# Z80_Interface.net
KiCad netlist of a schematic drawn in Altium Designer
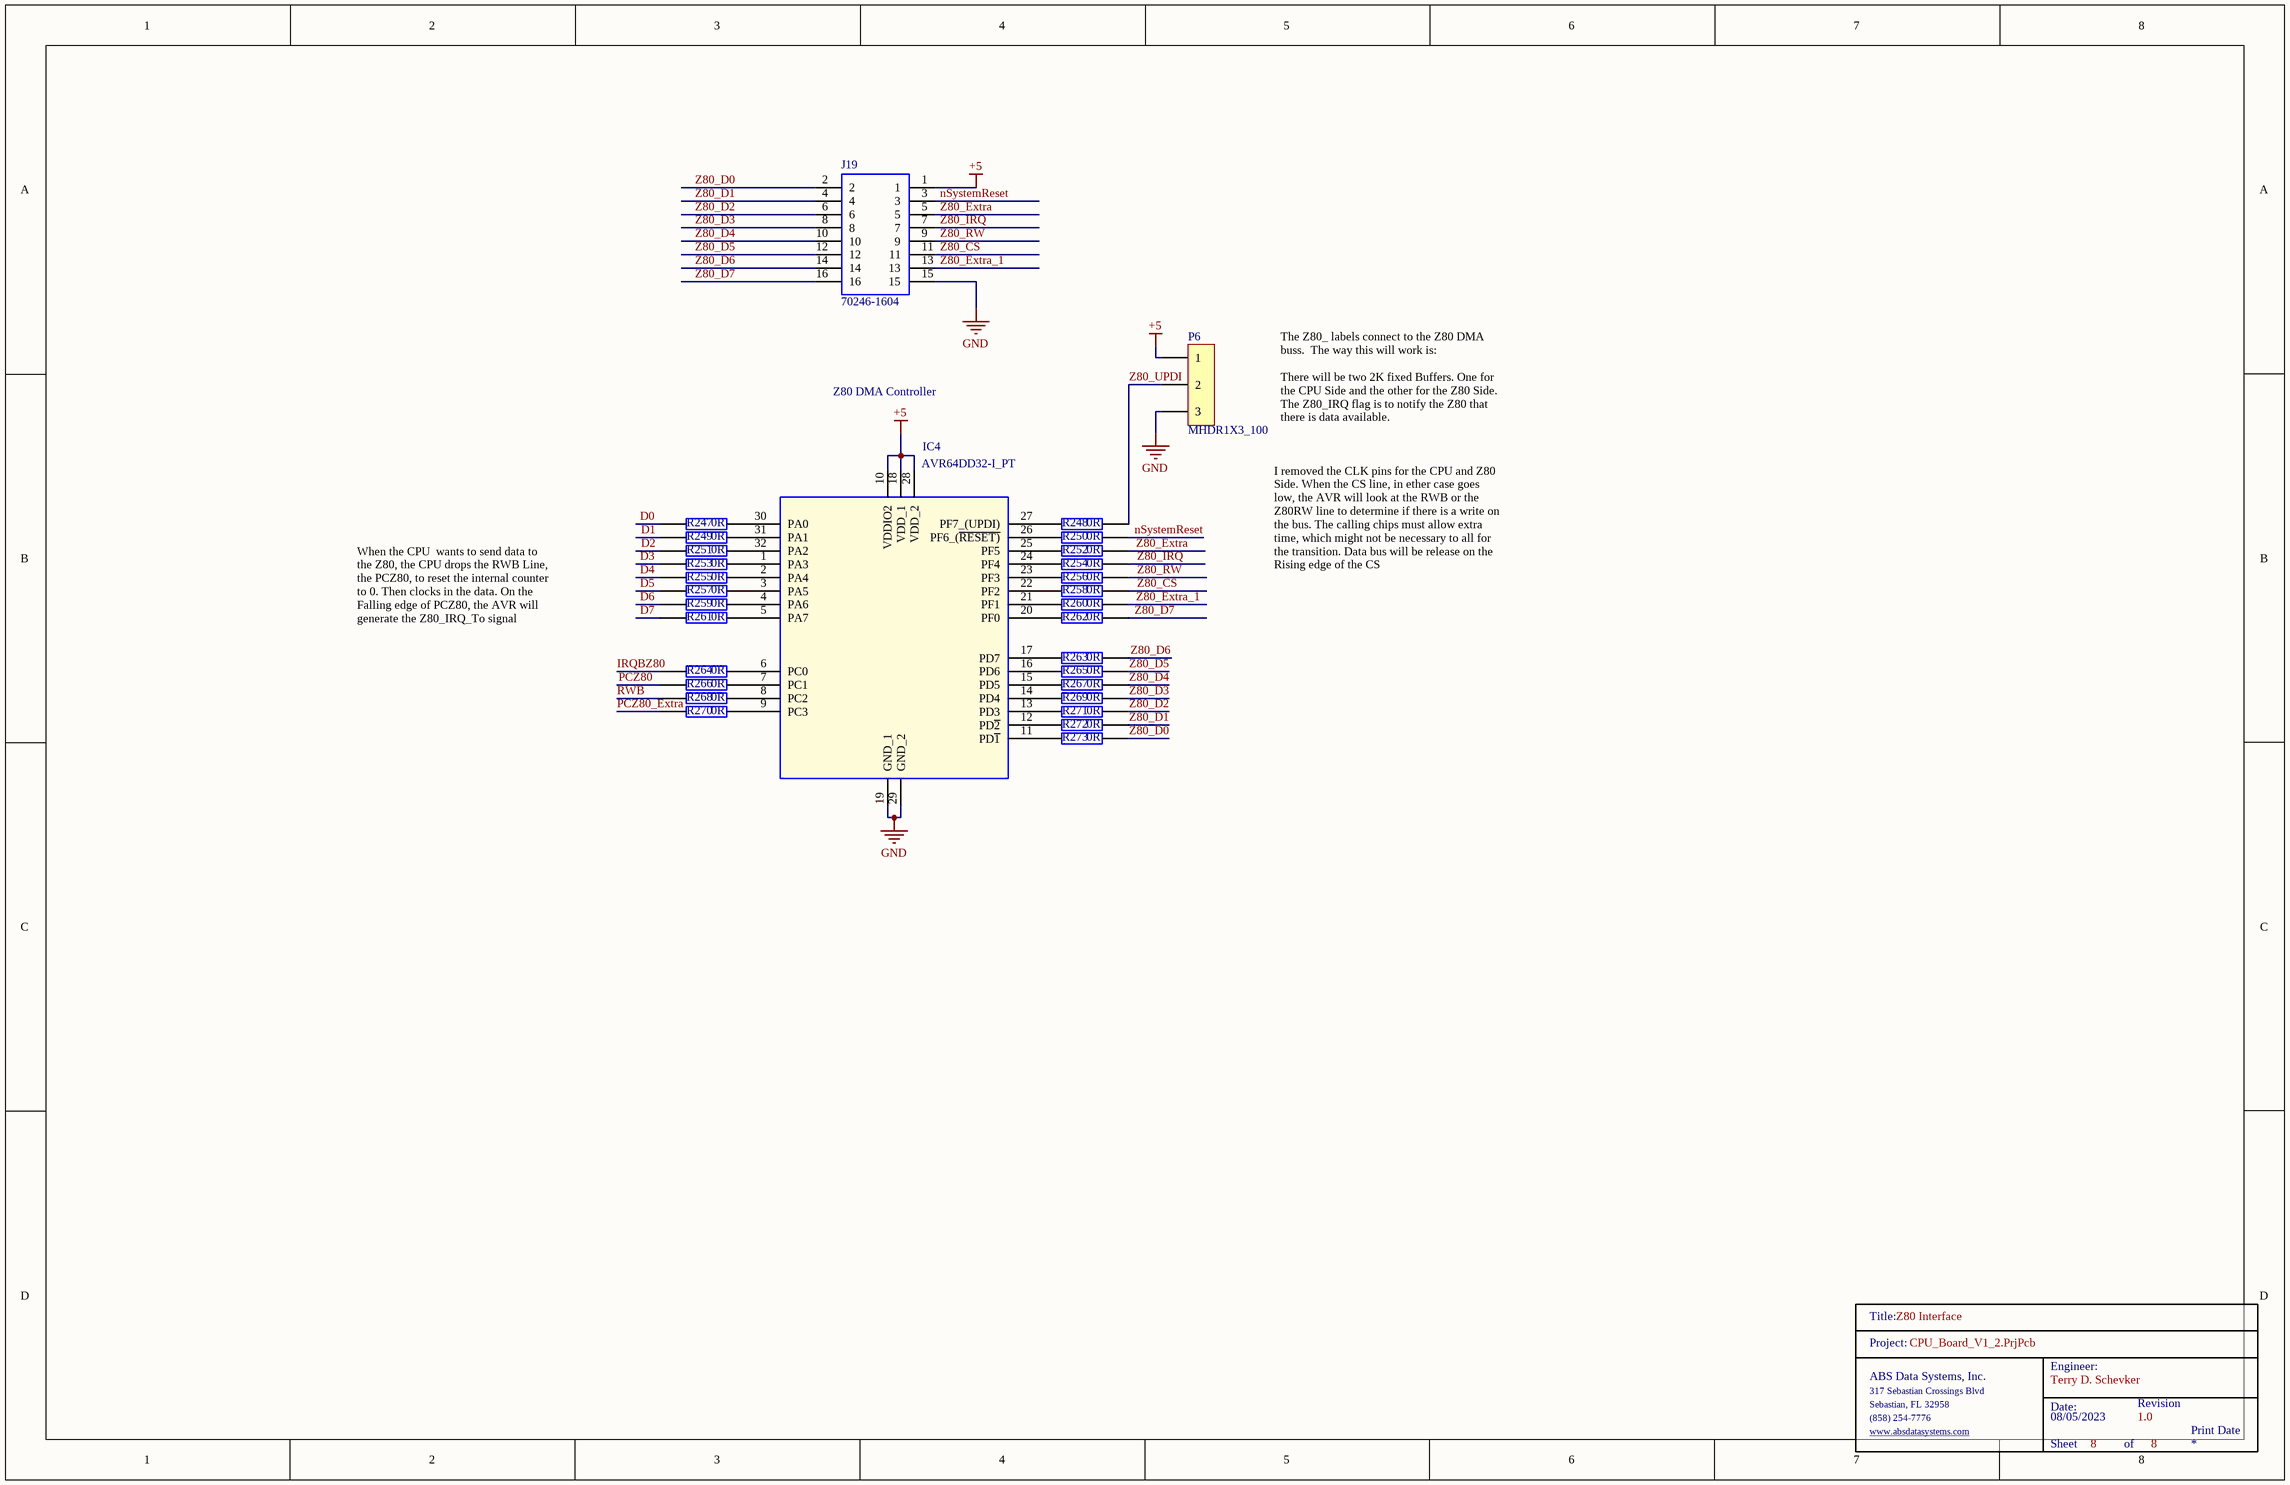
[diagram p0: Z80_Interface.SchDoc]

(export (version "E")
  (design (tool "Eeschema 10.0.6"))
  (components
    (comp (ref "IC4")
      (value "AVR64DD32-I_PT")
      (footprint "CPU_Memory:QFP80P900X900X120-32N")
      (description "Integrated Circuit")
      (fields (field (name "MANUFACTURER_PART_NUMBER") "AVR64DD32-I/PT ¦ MULTI-VOLTAGE I/O"))
      (libsource (lib "CPU_Memory") (part "AVR64DD32-I_PT"))
    )
    (comp (ref "J19")
      (value "70246-1604")
      (footprint "SHDR16W99P254_2X8_2794X889X927P")
      (description "Molex C-GRID 70246, 2.54mm Pitch, 16 Way, 2 Row, Straight PCB Header, Through Hole")
      (fields (field (name "MOUSER PART NUMBER") "538-70246-1604"))
      (libsource (lib "Connectors") (part "70246-1604"))
    )
    (comp (ref "P6")
      (value "MHDR1X3_100")
      (footprint "MHDR1X3_100")
      (description "Header, 3-Pin")
      (fields (field (name "PUBLISHER") "Altium Limited"))
      (libsource (lib "Connectors") (part "MHDR1X3_100"))
    )
    (comp (ref "R247")
      (value "0R")
      (footprint "0603")
      (description "YAGEO 0603 0 ohm")
      (fields
        (field (name "MOUSER PART NUMBER") "603-RC0603JR-070RL")
        (field (name "MANUFACTURER_PART_NUMBER") "RC0603JR-070RL")
      )
      (libsource (lib "Resistors") (part "RC0603JR-070RL"))
    )
    (comp (ref "R248")
      (value "0R")
      (footprint "0603")
      (description "YAGEO 0603 0 ohm")
      (fields
        (field (name "MOUSER PART NUMBER") "603-RC0603JR-070RL")
        (field (name "MANUFACTURER_PART_NUMBER") "RC0603JR-070RL")
      )
      (libsource (lib "Resistors") (part "RC0603JR-070RL"))
    )
    (comp (ref "R249")
      (value "0R")
      (footprint "0603")
      (description "YAGEO 0603 0 ohm")
      (fields
        (field (name "MOUSER PART NUMBER") "603-RC0603JR-070RL")
        (field (name "MANUFACTURER_PART_NUMBER") "RC0603JR-070RL")
      )
      (libsource (lib "Resistors") (part "RC0603JR-070RL"))
    )
    (comp (ref "R250")
      (value "0R")
      (footprint "0603")
      (description "YAGEO 0603 0 ohm")
      (fields
        (field (name "MOUSER PART NUMBER") "603-RC0603JR-070RL")
        (field (name "MANUFACTURER_PART_NUMBER") "RC0603JR-070RL")
      )
      (libsource (lib "Resistors") (part "RC0603JR-070RL"))
    )
    (comp (ref "R251")
      (value "0R")
      (footprint "0603")
      (description "YAGEO 0603 0 ohm")
      (fields
        (field (name "MOUSER PART NUMBER") "603-RC0603JR-070RL")
        (field (name "MANUFACTURER_PART_NUMBER") "RC0603JR-070RL")
      )
      (libsource (lib "Resistors") (part "RC0603JR-070RL"))
    )
    (comp (ref "R252")
      (value "0R")
      (footprint "0603")
      (description "YAGEO 0603 0 ohm")
      (fields
        (field (name "MOUSER PART NUMBER") "603-RC0603JR-070RL")
        (field (name "MANUFACTURER_PART_NUMBER") "RC0603JR-070RL")
      )
      (libsource (lib "Resistors") (part "RC0603JR-070RL"))
    )
    (comp (ref "R253")
      (value "0R")
      (footprint "0603")
      (description "YAGEO 0603 0 ohm")
      (fields
        (field (name "MOUSER PART NUMBER") "603-RC0603JR-070RL")
        (field (name "MANUFACTURER_PART_NUMBER") "RC0603JR-070RL")
      )
      (libsource (lib "Resistors") (part "RC0603JR-070RL"))
    )
    (comp (ref "R254")
      (value "0R")
      (footprint "0603")
      (description "YAGEO 0603 0 ohm")
      (fields
        (field (name "MOUSER PART NUMBER") "603-RC0603JR-070RL")
        (field (name "MANUFACTURER_PART_NUMBER") "RC0603JR-070RL")
      )
      (libsource (lib "Resistors") (part "RC0603JR-070RL"))
    )
    (comp (ref "R255")
      (value "0R")
      (footprint "0603")
      (description "YAGEO 0603 0 ohm")
      (fields
        (field (name "MOUSER PART NUMBER") "603-RC0603JR-070RL")
        (field (name "MANUFACTURER_PART_NUMBER") "RC0603JR-070RL")
      )
      (libsource (lib "Resistors") (part "RC0603JR-070RL"))
    )
    (comp (ref "R256")
      (value "0R")
      (footprint "0603")
      (description "YAGEO 0603 0 ohm")
      (fields
        (field (name "MOUSER PART NUMBER") "603-RC0603JR-070RL")
        (field (name "MANUFACTURER_PART_NUMBER") "RC0603JR-070RL")
      )
      (libsource (lib "Resistors") (part "RC0603JR-070RL"))
    )
    (comp (ref "R257")
      (value "0R")
      (footprint "0603")
      (description "YAGEO 0603 0 ohm")
      (fields
        (field (name "MOUSER PART NUMBER") "603-RC0603JR-070RL")
        (field (name "MANUFACTURER_PART_NUMBER") "RC0603JR-070RL")
      )
      (libsource (lib "Resistors") (part "RC0603JR-070RL"))
    )
    (comp (ref "R258")
      (value "0R")
      (footprint "0603")
      (description "YAGEO 0603 0 ohm")
      (fields
        (field (name "MOUSER PART NUMBER") "603-RC0603JR-070RL")
        (field (name "MANUFACTURER_PART_NUMBER") "RC0603JR-070RL")
      )
      (libsource (lib "Resistors") (part "RC0603JR-070RL"))
    )
    (comp (ref "R259")
      (value "0R")
      (footprint "0603")
      (description "YAGEO 0603 0 ohm")
      (fields
        (field (name "MOUSER PART NUMBER") "603-RC0603JR-070RL")
        (field (name "MANUFACTURER_PART_NUMBER") "RC0603JR-070RL")
      )
      (libsource (lib "Resistors") (part "RC0603JR-070RL"))
    )
    (comp (ref "R260")
      (value "0R")
      (footprint "0603")
      (description "YAGEO 0603 0 ohm")
      (fields
        (field (name "MOUSER PART NUMBER") "603-RC0603JR-070RL")
        (field (name "MANUFACTURER_PART_NUMBER") "RC0603JR-070RL")
      )
      (libsource (lib "Resistors") (part "RC0603JR-070RL"))
    )
    (comp (ref "R261")
      (value "0R")
      (footprint "0603")
      (description "YAGEO 0603 0 ohm")
      (fields
        (field (name "MOUSER PART NUMBER") "603-RC0603JR-070RL")
        (field (name "MANUFACTURER_PART_NUMBER") "RC0603JR-070RL")
      )
      (libsource (lib "Resistors") (part "RC0603JR-070RL"))
    )
    (comp (ref "R262")
      (value "0R")
      (footprint "0603")
      (description "YAGEO 0603 0 ohm")
      (fields
        (field (name "MOUSER PART NUMBER") "603-RC0603JR-070RL")
        (field (name "MANUFACTURER_PART_NUMBER") "RC0603JR-070RL")
      )
      (libsource (lib "Resistors") (part "RC0603JR-070RL"))
    )
    (comp (ref "R263")
      (value "0R")
      (footprint "0603")
      (description "YAGEO 0603 0 ohm")
      (fields
        (field (name "MOUSER PART NUMBER") "603-RC0603JR-070RL")
        (field (name "MANUFACTURER_PART_NUMBER") "RC0603JR-070RL")
      )
      (libsource (lib "Resistors") (part "RC0603JR-070RL"))
    )
    (comp (ref "R264")
      (value "0R")
      (footprint "0603")
      (description "YAGEO 0603 0 ohm")
      (fields
        (field (name "MOUSER PART NUMBER") "603-RC0603JR-070RL")
        (field (name "MANUFACTURER_PART_NUMBER") "RC0603JR-070RL")
      )
      (libsource (lib "Resistors") (part "RC0603JR-070RL"))
    )
    (comp (ref "R265")
      (value "0R")
      (footprint "0603")
      (description "YAGEO 0603 0 ohm")
      (fields
        (field (name "MOUSER PART NUMBER") "603-RC0603JR-070RL")
        (field (name "MANUFACTURER_PART_NUMBER") "RC0603JR-070RL")
      )
      (libsource (lib "Resistors") (part "RC0603JR-070RL"))
    )
    (comp (ref "R266")
      (value "0R")
      (footprint "0603")
      (description "YAGEO 0603 0 ohm")
      (fields
        (field (name "MOUSER PART NUMBER") "603-RC0603JR-070RL")
        (field (name "MANUFACTURER_PART_NUMBER") "RC0603JR-070RL")
      )
      (libsource (lib "Resistors") (part "RC0603JR-070RL"))
    )
    (comp (ref "R267")
      (value "0R")
      (footprint "0603")
      (description "YAGEO 0603 0 ohm")
      (fields
        (field (name "MOUSER PART NUMBER") "603-RC0603JR-070RL")
        (field (name "MANUFACTURER_PART_NUMBER") "RC0603JR-070RL")
      )
      (libsource (lib "Resistors") (part "RC0603JR-070RL"))
    )
    (comp (ref "R268")
      (value "0R")
      (footprint "0603")
      (description "YAGEO 0603 0 ohm")
      (fields
        (field (name "MOUSER PART NUMBER") "603-RC0603JR-070RL")
        (field (name "MANUFACTURER_PART_NUMBER") "RC0603JR-070RL")
      )
      (libsource (lib "Resistors") (part "RC0603JR-070RL"))
    )
    (comp (ref "R269")
      (value "0R")
      (footprint "0603")
      (description "YAGEO 0603 0 ohm")
      (fields
        (field (name "MOUSER PART NUMBER") "603-RC0603JR-070RL")
        (field (name "MANUFACTURER_PART_NUMBER") "RC0603JR-070RL")
      )
      (libsource (lib "Resistors") (part "RC0603JR-070RL"))
    )
    (comp (ref "R270")
      (value "0R")
      (footprint "0603")
      (description "YAGEO 0603 0 ohm")
      (fields
        (field (name "MOUSER PART NUMBER") "603-RC0603JR-070RL")
        (field (name "MANUFACTURER_PART_NUMBER") "RC0603JR-070RL")
      )
      (libsource (lib "Resistors") (part "RC0603JR-070RL"))
    )
    (comp (ref "R271")
      (value "0R")
      (footprint "0603")
      (description "YAGEO 0603 0 ohm")
      (fields
        (field (name "MOUSER PART NUMBER") "603-RC0603JR-070RL")
        (field (name "MANUFACTURER_PART_NUMBER") "RC0603JR-070RL")
      )
      (libsource (lib "Resistors") (part "RC0603JR-070RL"))
    )
    (comp (ref "R272")
      (value "0R")
      (footprint "0603")
      (description "YAGEO 0603 0 ohm")
      (fields
        (field (name "MOUSER PART NUMBER") "603-RC0603JR-070RL")
        (field (name "MANUFACTURER_PART_NUMBER") "RC0603JR-070RL")
      )
      (libsource (lib "Resistors") (part "RC0603JR-070RL"))
    )
    (comp (ref "R273")
      (value "0R")
      (footprint "0603")
      (description "YAGEO 0603 0 ohm")
      (fields
        (field (name "MOUSER PART NUMBER") "603-RC0603JR-070RL")
        (field (name "MANUFACTURER_PART_NUMBER") "RC0603JR-070RL")
      )
      (libsource (lib "Resistors") (part "RC0603JR-070RL"))
    )
  )
  (nets
    (net (code "1") (name "+5") (class "Default")
      (node (ref "IC4") (pin "10") (pinfunction "VDDIO2_10") (pintype "passive"))
      (node (ref "IC4") (pin "18") (pinfunction "VDD_1_18") (pintype "passive"))
      (node (ref "IC4") (pin "28") (pinfunction "VDD_2_28") (pintype "passive"))
      (node (ref "J19") (pin "1") (pinfunction "1_1") (pintype "passive"))
      (node (ref "P6") (pin "1") (pinfunction "1_1") (pintype "passive"))
    )
    (net (code "2") (name "/D0") (class "Default")
      (node (ref "R247") (pin "1") (pinfunction "1_1") (pintype "passive"))
    )
    (net (code "3") (name "/D1") (class "Default")
      (node (ref "R249") (pin "1") (pinfunction "1_1") (pintype "passive"))
    )
    (net (code "4") (name "/D2") (class "Default")
      (node (ref "R251") (pin "1") (pinfunction "1_1") (pintype "passive"))
    )
    (net (code "5") (name "/D3") (class "Default")
      (node (ref "R253") (pin "1") (pinfunction "1_1") (pintype "passive"))
    )
    (net (code "6") (name "/D4") (class "Default")
      (node (ref "R255") (pin "1") (pinfunction "1_1") (pintype "passive"))
    )
    (net (code "7") (name "/D5") (class "Default")
      (node (ref "R257") (pin "1") (pinfunction "1_1") (pintype "passive"))
    )
    (net (code "8") (name "/D6") (class "Default")
      (node (ref "R259") (pin "1") (pinfunction "1_1") (pintype "passive"))
    )
    (net (code "9") (name "/D7") (class "Default")
      (node (ref "R261") (pin "1") (pinfunction "1_1") (pintype "passive"))
    )
    (net (code "10") (name "/IRQBZ80") (class "Default")
      (node (ref "R264") (pin "1") (pinfunction "1_1") (pintype "passive"))
    )
    (net (code "11") (name "/PCZ80") (class "Default")
      (node (ref "R266") (pin "1") (pinfunction "1_1") (pintype "passive"))
    )
    (net (code "12") (name "/PCZ80_Extra") (class "Default")
      (node (ref "R270") (pin "1") (pinfunction "1_1") (pintype "passive"))
    )
    (net (code "13") (name "/RWB") (class "Default")
      (node (ref "R268") (pin "1") (pinfunction "1_1") (pintype "passive"))
    )
    (net (code "14") (name "/Z80_CS") (class "Default")
      (node (ref "J19") (pin "11") (pinfunction "11_11") (pintype "passive"))
      (node (ref "R258") (pin "2") (pinfunction "2_2") (pintype "passive"))
    )
    (net (code "15") (name "/Z80_D0") (class "Default")
      (node (ref "J19") (pin "2") (pinfunction "2_2") (pintype "passive"))
      (node (ref "R273") (pin "2") (pinfunction "2_2") (pintype "passive"))
    )
    (net (code "16") (name "/Z80_D1") (class "Default")
      (node (ref "J19") (pin "4") (pinfunction "4_4") (pintype "passive"))
      (node (ref "R272") (pin "2") (pinfunction "2_2") (pintype "passive"))
    )
    (net (code "17") (name "/Z80_D2") (class "Default")
      (node (ref "J19") (pin "6") (pinfunction "6_6") (pintype "passive"))
      (node (ref "R271") (pin "2") (pinfunction "2_2") (pintype "passive"))
    )
    (net (code "18") (name "/Z80_D3") (class "Default")
      (node (ref "J19") (pin "8") (pinfunction "8_8") (pintype "passive"))
      (node (ref "R269") (pin "2") (pinfunction "2_2") (pintype "passive"))
    )
    (net (code "19") (name "/Z80_D4") (class "Default")
      (node (ref "J19") (pin "10") (pinfunction "10_10") (pintype "passive"))
      (node (ref "R267") (pin "2") (pinfunction "2_2") (pintype "passive"))
    )
    (net (code "20") (name "/Z80_D5") (class "Default")
      (node (ref "J19") (pin "12") (pinfunction "12_12") (pintype "passive"))
      (node (ref "R265") (pin "2") (pinfunction "2_2") (pintype "passive"))
    )
    (net (code "21") (name "/Z80_D6") (class "Default")
      (node (ref "J19") (pin "14") (pinfunction "14_14") (pintype "passive"))
      (node (ref "R263") (pin "2") (pinfunction "2_2") (pintype "passive"))
    )
    (net (code "22") (name "/Z80_D7") (class "Default")
      (node (ref "J19") (pin "16") (pinfunction "16_16") (pintype "passive"))
      (node (ref "R262") (pin "2") (pinfunction "2_2") (pintype "passive"))
    )
    (net (code "23") (name "/Z80_Extra") (class "Default")
      (node (ref "J19") (pin "5") (pinfunction "5_5") (pintype "passive"))
      (node (ref "R252") (pin "2") (pinfunction "2_2") (pintype "passive"))
    )
    (net (code "24") (name "/Z80_Extra_1") (class "Default")
      (node (ref "J19") (pin "13") (pinfunction "13_13") (pintype "passive"))
      (node (ref "R260") (pin "2") (pinfunction "2_2") (pintype "passive"))
    )
    (net (code "25") (name "/Z80_IRQ") (class "Default")
      (node (ref "J19") (pin "7") (pinfunction "7_7") (pintype "passive"))
      (node (ref "R254") (pin "2") (pinfunction "2_2") (pintype "passive"))
    )
    (net (code "26") (name "/Z80_RW") (class "Default")
      (node (ref "J19") (pin "9") (pinfunction "9_9") (pintype "passive"))
      (node (ref "R256") (pin "2") (pinfunction "2_2") (pintype "passive"))
    )
    (net (code "27") (name "/Z80_UPDI") (class "Default")
      (node (ref "P6") (pin "2") (pinfunction "2_2") (pintype "passive"))
      (node (ref "R248") (pin "2") (pinfunction "2_2") (pintype "passive"))
    )
    (net (code "28") (name "/nSystemReset") (class "Default")
      (node (ref "J19") (pin "3") (pinfunction "3_3") (pintype "passive"))
      (node (ref "R250") (pin "2") (pinfunction "2_2") (pintype "passive"))
    )
    (net (code "29") (name "GND") (class "Default")
      (node (ref "IC4") (pin "19") (pinfunction "GND_1_19") (pintype "passive"))
      (node (ref "IC4") (pin "29") (pinfunction "GND_2_29") (pintype "passive"))
      (node (ref "J19") (pin "15") (pinfunction "15_15") (pintype "passive"))
      (node (ref "P6") (pin "3") (pinfunction "3_3") (pintype "passive"))
    )
    (net (code "30") (name "Net-(IC4-PA0)") (class "Default")
      (node (ref "IC4") (pin "30") (pinfunction "PA0_30") (pintype "passive"))
      (node (ref "R247") (pin "2") (pinfunction "2_2") (pintype "passive"))
    )
    (net (code "31") (name "Net-(IC4-PA1)") (class "Default")
      (node (ref "IC4") (pin "31") (pinfunction "PA1_31") (pintype "passive"))
      (node (ref "R249") (pin "2") (pinfunction "2_2") (pintype "passive"))
    )
    (net (code "32") (name "Net-(IC4-PA2)") (class "Default")
      (node (ref "IC4") (pin "32") (pinfunction "PA2_32") (pintype "passive"))
      (node (ref "R251") (pin "2") (pinfunction "2_2") (pintype "passive"))
    )
    (net (code "33") (name "Net-(IC4-PA3)") (class "Default")
      (node (ref "IC4") (pin "1") (pinfunction "PA3_1") (pintype "passive"))
      (node (ref "R253") (pin "2") (pinfunction "2_2") (pintype "passive"))
    )
    (net (code "34") (name "Net-(IC4-PA4)") (class "Default")
      (node (ref "IC4") (pin "2") (pinfunction "PA4_2") (pintype "passive"))
      (node (ref "R255") (pin "2") (pinfunction "2_2") (pintype "passive"))
    )
    (net (code "35") (name "Net-(IC4-PA5)") (class "Default")
      (node (ref "IC4") (pin "3") (pinfunction "PA5_3") (pintype "passive"))
      (node (ref "R257") (pin "2") (pinfunction "2_2") (pintype "passive"))
    )
    (net (code "36") (name "Net-(IC4-PA6)") (class "Default")
      (node (ref "IC4") (pin "4") (pinfunction "PA6_4") (pintype "passive"))
      (node (ref "R259") (pin "2") (pinfunction "2_2") (pintype "passive"))
    )
    (net (code "37") (name "Net-(IC4-PA7)") (class "Default")
      (node (ref "IC4") (pin "5") (pinfunction "PA7_5") (pintype "passive"))
      (node (ref "R261") (pin "2") (pinfunction "2_2") (pintype "passive"))
    )
    (net (code "38") (name "Net-(IC4-PC0)") (class "Default")
      (node (ref "IC4") (pin "6") (pinfunction "PC0_6") (pintype "passive"))
      (node (ref "R264") (pin "2") (pinfunction "2_2") (pintype "passive"))
    )
    (net (code "39") (name "Net-(IC4-PC1)") (class "Default")
      (node (ref "IC4") (pin "7") (pinfunction "PC1_7") (pintype "passive"))
      (node (ref "R266") (pin "2") (pinfunction "2_2") (pintype "passive"))
    )
    (net (code "40") (name "Net-(IC4-PC2)") (class "Default")
      (node (ref "IC4") (pin "8") (pinfunction "PC2_8") (pintype "passive"))
      (node (ref "R268") (pin "2") (pinfunction "2_2") (pintype "passive"))
    )
    (net (code "41") (name "Net-(IC4-PC3)") (class "Default")
      (node (ref "IC4") (pin "9") (pinfunction "PC3_9") (pintype "passive"))
      (node (ref "R270") (pin "2") (pinfunction "2_2") (pintype "passive"))
    )
    (net (code "42") (name "Net-(IC4-PD3)") (class "Default")
      (node (ref "IC4") (pin "13") (pinfunction "PD3_13") (pintype "passive"))
      (node (ref "R271") (pin "1") (pinfunction "1_1") (pintype "passive"))
    )
    (net (code "43") (name "Net-(IC4-PD4)") (class "Default")
      (node (ref "IC4") (pin "14") (pinfunction "PD4_14") (pintype "passive"))
      (node (ref "R269") (pin "1") (pinfunction "1_1") (pintype "passive"))
    )
    (net (code "44") (name "Net-(IC4-PD5)") (class "Default")
      (node (ref "IC4") (pin "15") (pinfunction "PD5_15") (pintype "passive"))
      (node (ref "R267") (pin "1") (pinfunction "1_1") (pintype "passive"))
    )
    (net (code "45") (name "Net-(IC4-PD6)") (class "Default")
      (node (ref "IC4") (pin "16") (pinfunction "PD6_16") (pintype "passive"))
      (node (ref "R265") (pin "1") (pinfunction "1_1") (pintype "passive"))
    )
    (net (code "46") (name "Net-(IC4-PD7)") (class "Default")
      (node (ref "IC4") (pin "17") (pinfunction "PD7_17") (pintype "passive"))
      (node (ref "R263") (pin "1") (pinfunction "1_1") (pintype "passive"))
    )
    (net (code "47") (name "Net-(IC4-PD~{1})") (class "Default")
      (node (ref "IC4") (pin "11") (pinfunction "PD~{1}_11") (pintype "passive"))
      (node (ref "R273") (pin "1") (pinfunction "1_1") (pintype "passive"))
    )
    (net (code "48") (name "Net-(IC4-PD~{2})") (class "Default")
      (node (ref "IC4") (pin "12") (pinfunction "PD~{2}_12") (pintype "passive"))
      (node (ref "R272") (pin "1") (pinfunction "1_1") (pintype "passive"))
    )
    (net (code "49") (name "Net-(IC4-PF0)") (class "Default")
      (node (ref "IC4") (pin "20") (pinfunction "PF0_20") (pintype "passive"))
      (node (ref "R262") (pin "1") (pinfunction "1_1") (pintype "passive"))
    )
    (net (code "50") (name "Net-(IC4-PF1)") (class "Default")
      (node (ref "IC4") (pin "21") (pinfunction "PF1_21") (pintype "passive"))
      (node (ref "R260") (pin "1") (pinfunction "1_1") (pintype "passive"))
    )
    (net (code "51") (name "Net-(IC4-PF2)") (class "Default")
      (node (ref "IC4") (pin "22") (pinfunction "PF2_22") (pintype "passive"))
      (node (ref "R258") (pin "1") (pinfunction "1_1") (pintype "passive"))
    )
    (net (code "52") (name "Net-(IC4-PF3)") (class "Default")
      (node (ref "IC4") (pin "23") (pinfunction "PF3_23") (pintype "passive"))
      (node (ref "R256") (pin "1") (pinfunction "1_1") (pintype "passive"))
    )
    (net (code "53") (name "Net-(IC4-PF4)") (class "Default")
      (node (ref "IC4") (pin "24") (pinfunction "PF4_24") (pintype "passive"))
      (node (ref "R254") (pin "1") (pinfunction "1_1") (pintype "passive"))
    )
    (net (code "54") (name "Net-(IC4-PF5)") (class "Default")
      (node (ref "IC4") (pin "25") (pinfunction "PF5_25") (pintype "passive"))
      (node (ref "R252") (pin "1") (pinfunction "1_1") (pintype "passive"))
    )
    (net (code "55") (name "Net-(IC4-PF6_(~{RESET)})") (class "Default")
      (node (ref "IC4") (pin "26") (pinfunction "PF6_(~{RESET)}_26") (pintype "passive"))
      (node (ref "R250") (pin "1") (pinfunction "1_1") (pintype "passive"))
    )
    (net (code "56") (name "Net-(IC4-PF7_(UPDI))") (class "Default")
      (node (ref "IC4") (pin "27") (pinfunction "PF7_(UPDI)_27") (pintype "passive"))
      (node (ref "R248") (pin "1") (pinfunction "1_1") (pintype "passive"))
    )
  )
)
